# untitled.net
KiCad netlist of a schematic drawn in EAGLE
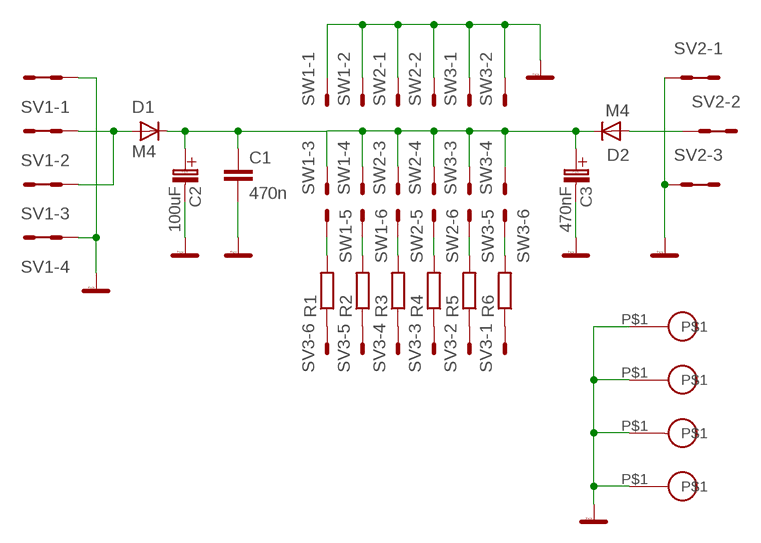
[diagram p0: schematic, sheet 1]

(export (version "E")
  (design (tool "Eeschema 10.0.6"))
  (components
    (comp (ref "C1")
      (value "470n")
      (footprint "eagle-import:C0805")
      (libsource (lib "eagle-import") (part "C-EUC0805"))
    )
    (comp (ref "C2")
      (value "100uF")
      (footprint "eagle-import:C")
      (libsource (lib "eagle-import") (part "1M/50V"))
    )
    (comp (ref "C3")
      (value "470nF")
      (footprint "eagle-import:C")
      (libsource (lib "eagle-import") (part "1M/50V"))
    )
    (comp (ref "D1")
      (value "M4")
      (footprint "eagle-import:SMA")
      (libsource (lib "eagle-import") (part "D-OB.SMA"))
    )
    (comp (ref "D2")
      (value "M4")
      (footprint "eagle-import:SMA")
      (libsource (lib "eagle-import") (part "D-OB.SMA"))
    )
    (comp (ref "R1")
      (value "R0805")
      (footprint "eagle-import:0805")
      (libsource (lib "eagle-import") (part "R0805"))
    )
    (comp (ref "R2")
      (value "R0805")
      (footprint "eagle-import:0805")
      (libsource (lib "eagle-import") (part "R0805"))
    )
    (comp (ref "R3")
      (value "R0805")
      (footprint "eagle-import:0805")
      (libsource (lib "eagle-import") (part "R0805"))
    )
    (comp (ref "R4")
      (value "R0805")
      (footprint "eagle-import:0805")
      (libsource (lib "eagle-import") (part "R0805"))
    )
    (comp (ref "R5")
      (value "R0805")
      (footprint "eagle-import:0805")
      (libsource (lib "eagle-import") (part "R0805"))
    )
    (comp (ref "R6")
      (value "R0805")
      (footprint "eagle-import:0805")
      (libsource (lib "eagle-import") (part "R0805"))
    )
    (comp (ref "SV1")
      (value "MA04-2")
      (footprint "eagle-import:MA04-2")
      (libsource (lib "eagle-import") (part "MA04-2"))
    )
    (comp (ref "SV2")
      (value "MA03-2")
      (footprint "eagle-import:MA03-2")
      (libsource (lib "eagle-import") (part "MA03-2"))
    )
    (comp (ref "SV3")
      (value "MA06-1")
      (footprint "eagle-import:MA06-1")
      (libsource (lib "eagle-import") (part "MA06-1"))
    )
    (comp (ref "SW1")
      (value "MA03-3")
      (footprint "eagle-import:MA03-2")
      (libsource (lib "eagle-import") (part "MA03-3"))
    )
    (comp (ref "SW2")
      (value "MA03-3")
      (footprint "eagle-import:MA03-2")
      (libsource (lib "eagle-import") (part "MA03-3"))
    )
    (comp (ref "SW3")
      (value "MA03-3")
      (footprint "eagle-import:MA03-2")
      (libsource (lib "eagle-import") (part "MA03-3"))
    )
    (comp (ref "X1")
      (value "SROUB3M")
      (footprint "eagle-import:SROUB3M")
      (libsource (lib "eagle-import") (part "SROUB3M"))
    )
    (comp (ref "X2")
      (value "SROUB3M")
      (footprint "eagle-import:SROUB3M")
      (libsource (lib "eagle-import") (part "SROUB3M"))
    )
    (comp (ref "X3")
      (value "SROUB3M")
      (footprint "eagle-import:SROUB3M")
      (libsource (lib "eagle-import") (part "SROUB3M"))
    )
    (comp (ref "X4")
      (value "SROUB3M")
      (footprint "eagle-import:SROUB3M")
      (libsource (lib "eagle-import") (part "SROUB3M"))
    )
  )
  (nets
    (net (code "1") (name "GND") (class "Default")
      (node (ref "C1") (pin "2") (pinfunction "2_2") (pintype "passive"))
      (node (ref "C2") (pin "-") (pinfunction "C_EL-_-") (pintype "passive"))
      (node (ref "C3") (pin "-") (pinfunction "C_EL-_-") (pintype "passive"))
      (node (ref "SV1") (pin "1") (pinfunction "K_1") (pintype "passive"))
      (node (ref "SV1") (pin "2") (pinfunction "K_2") (pintype "passive"))
      (node (ref "SV1") (pin "7") (pinfunction "K_7") (pintype "passive"))
      (node (ref "SV1") (pin "8") (pinfunction "K_8") (pintype "passive"))
      (node (ref "SV2") (pin "1") (pinfunction "K_1") (pintype "passive"))
      (node (ref "SV2") (pin "2") (pinfunction "K_2") (pintype "passive"))
      (node (ref "SV2") (pin "5") (pinfunction "K_5") (pintype "passive"))
      (node (ref "SV2") (pin "6") (pinfunction "K_6") (pintype "passive"))
      (node (ref "SW1") (pin "1") (pinfunction "P$1_1") (pintype "passive"))
      (node (ref "SW1") (pin "2") (pinfunction "P$1_2") (pintype "passive"))
      (node (ref "SW2") (pin "1") (pinfunction "P$1_1") (pintype "passive"))
      (node (ref "SW2") (pin "2") (pinfunction "P$1_2") (pintype "passive"))
      (node (ref "SW3") (pin "1") (pinfunction "P$1_1") (pintype "passive"))
      (node (ref "SW3") (pin "2") (pinfunction "P$1_2") (pintype "passive"))
      (node (ref "X1") (pin "P$1") (pinfunction "P$1_P$1") (pintype "output"))
      (node (ref "X2") (pin "P$1") (pinfunction "P$1_P$1") (pintype "output"))
      (node (ref "X3") (pin "P$1") (pinfunction "P$1_P$1") (pintype "output"))
      (node (ref "X4") (pin "P$1") (pinfunction "P$1_P$1") (pintype "output"))
    )
    (net (code "2") (name "Net-(C2-C_EL+)") (class "Default")
      (node (ref "C1") (pin "1") (pinfunction "1_1") (pintype "passive"))
      (node (ref "C2") (pin "+") (pinfunction "C_EL+_+") (pintype "passive"))
      (node (ref "C3") (pin "+") (pinfunction "C_EL+_+") (pintype "passive"))
      (node (ref "D1") (pin "K") (pinfunction "C_K") (pintype "passive"))
      (node (ref "D2") (pin "K") (pinfunction "C_K") (pintype "passive"))
      (node (ref "SW1") (pin "3") (pinfunction "P$1_3") (pintype "passive"))
      (node (ref "SW1") (pin "4") (pinfunction "P$1_4") (pintype "passive"))
      (node (ref "SW2") (pin "3") (pinfunction "P$1_3") (pintype "passive"))
      (node (ref "SW2") (pin "4") (pinfunction "P$1_4") (pintype "passive"))
      (node (ref "SW3") (pin "3") (pinfunction "P$1_3") (pintype "passive"))
      (node (ref "SW3") (pin "4") (pinfunction "P$1_4") (pintype "passive"))
    )
    (net (code "3") (name "Net-(D1-PadA)") (class "Default")
      (node (ref "D1") (pin "A") (pinfunction "A_A") (pintype "passive"))
      (node (ref "SV1") (pin "3") (pinfunction "K_3") (pintype "passive"))
      (node (ref "SV1") (pin "4") (pinfunction "K_4") (pintype "passive"))
      (node (ref "SV1") (pin "5") (pinfunction "K_5") (pintype "passive"))
      (node (ref "SV1") (pin "6") (pinfunction "K_6") (pintype "passive"))
    )
    (net (code "4") (name "Net-(D2-PadA)") (class "Default")
      (node (ref "D2") (pin "A") (pinfunction "A_A") (pintype "passive"))
      (node (ref "SV2") (pin "3") (pinfunction "K_3") (pintype "passive"))
      (node (ref "SV2") (pin "4") (pinfunction "K_4") (pintype "passive"))
    )
    (net (code "5") (name "Net-(SV3A-P$1)") (class "Default")
      (node (ref "R6") (pin "1") (pinfunction "1_1") (pintype "passive"))
      (node (ref "SV3") (pin "1") (pinfunction "P$1_1") (pintype "passive"))
    )
    (net (code "6") (name "Net-(SV3B-P$1)") (class "Default")
      (node (ref "R5") (pin "1") (pinfunction "1_1") (pintype "passive"))
      (node (ref "SV3") (pin "2") (pinfunction "P$1_2") (pintype "passive"))
    )
    (net (code "7") (name "Net-(SV3C-P$1)") (class "Default")
      (node (ref "R4") (pin "1") (pinfunction "1_1") (pintype "passive"))
      (node (ref "SV3") (pin "3") (pinfunction "P$1_3") (pintype "passive"))
    )
    (net (code "8") (name "Net-(SV3D-P$1)") (class "Default")
      (node (ref "R3") (pin "1") (pinfunction "1_1") (pintype "passive"))
      (node (ref "SV3") (pin "4") (pinfunction "P$1_4") (pintype "passive"))
    )
    (net (code "9") (name "Net-(SV3E-P$1)") (class "Default")
      (node (ref "R2") (pin "1") (pinfunction "1_1") (pintype "passive"))
      (node (ref "SV3") (pin "5") (pinfunction "P$1_5") (pintype "passive"))
    )
    (net (code "10") (name "Net-(SV3F-P$1)") (class "Default")
      (node (ref "R1") (pin "1") (pinfunction "1_1") (pintype "passive"))
      (node (ref "SV3") (pin "6") (pinfunction "P$1_6") (pintype "passive"))
    )
    (net (code "11") (name "Net-(SW1E-P$1)") (class "Default")
      (node (ref "R1") (pin "2") (pinfunction "2_2") (pintype "passive"))
      (node (ref "SW1") (pin "5") (pinfunction "P$1_5") (pintype "passive"))
    )
    (net (code "12") (name "Net-(SW1F-P$1)") (class "Default")
      (node (ref "R2") (pin "2") (pinfunction "2_2") (pintype "passive"))
      (node (ref "SW1") (pin "6") (pinfunction "P$1_6") (pintype "passive"))
    )
    (net (code "13") (name "Net-(SW2E-P$1)") (class "Default")
      (node (ref "R3") (pin "2") (pinfunction "2_2") (pintype "passive"))
      (node (ref "SW2") (pin "5") (pinfunction "P$1_5") (pintype "passive"))
    )
    (net (code "14") (name "Net-(SW2F-P$1)") (class "Default")
      (node (ref "R4") (pin "2") (pinfunction "2_2") (pintype "passive"))
      (node (ref "SW2") (pin "6") (pinfunction "P$1_6") (pintype "passive"))
    )
    (net (code "15") (name "Net-(SW3E-P$1)") (class "Default")
      (node (ref "R5") (pin "2") (pinfunction "2_2") (pintype "passive"))
      (node (ref "SW3") (pin "5") (pinfunction "P$1_5") (pintype "passive"))
    )
    (net (code "16") (name "Net-(SW3F-P$1)") (class "Default")
      (node (ref "R6") (pin "2") (pinfunction "2_2") (pintype "passive"))
      (node (ref "SW3") (pin "6") (pinfunction "P$1_6") (pintype "passive"))
    )
  )
)
